# oresat-card.net
KiCad netlist of a schematic drawn in EAGLE
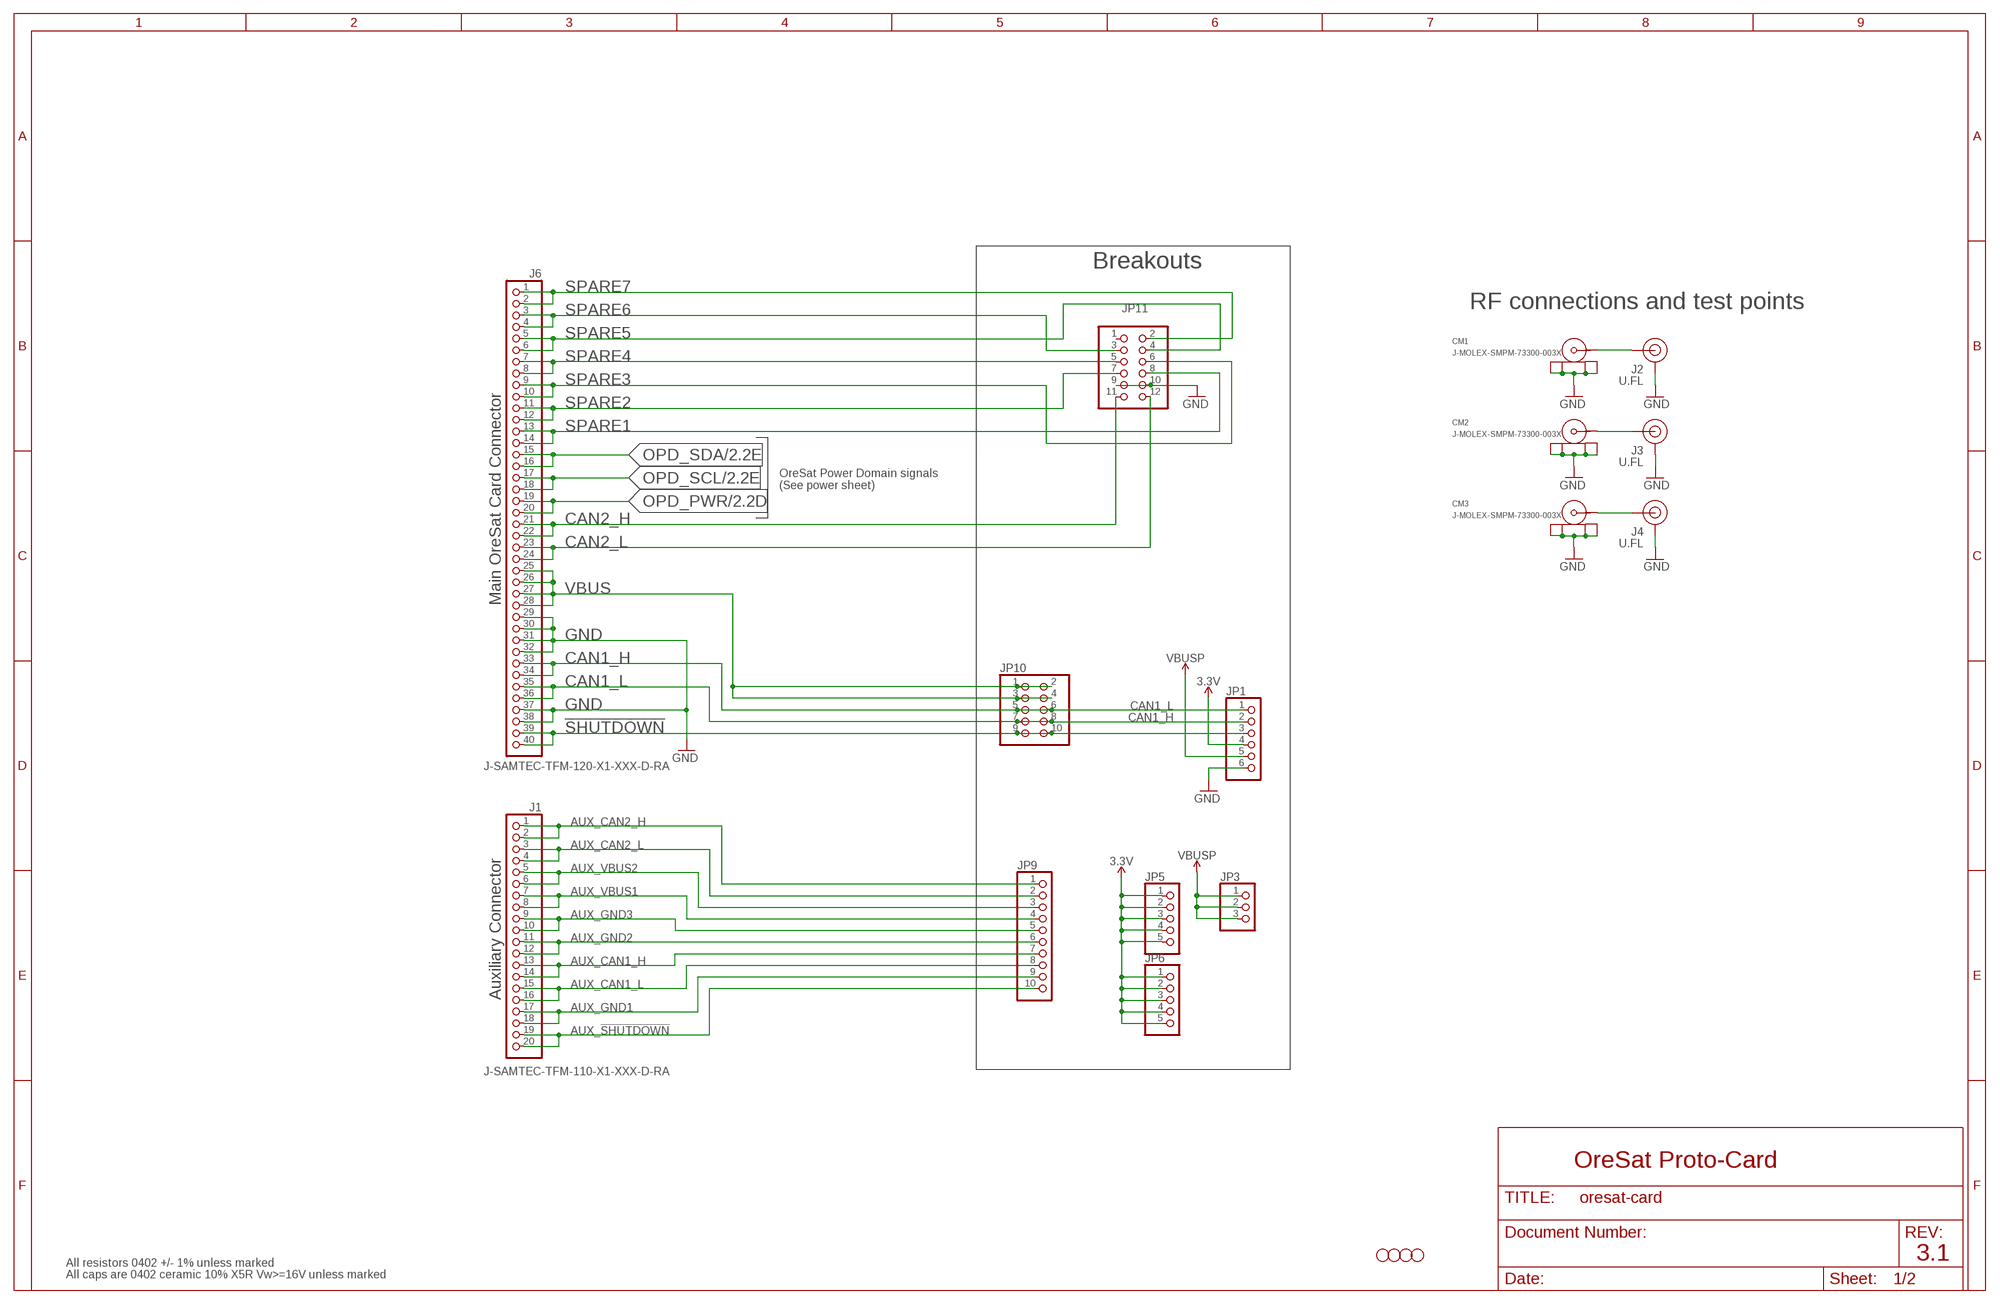
[diagram p0: schematic, sheet 1]
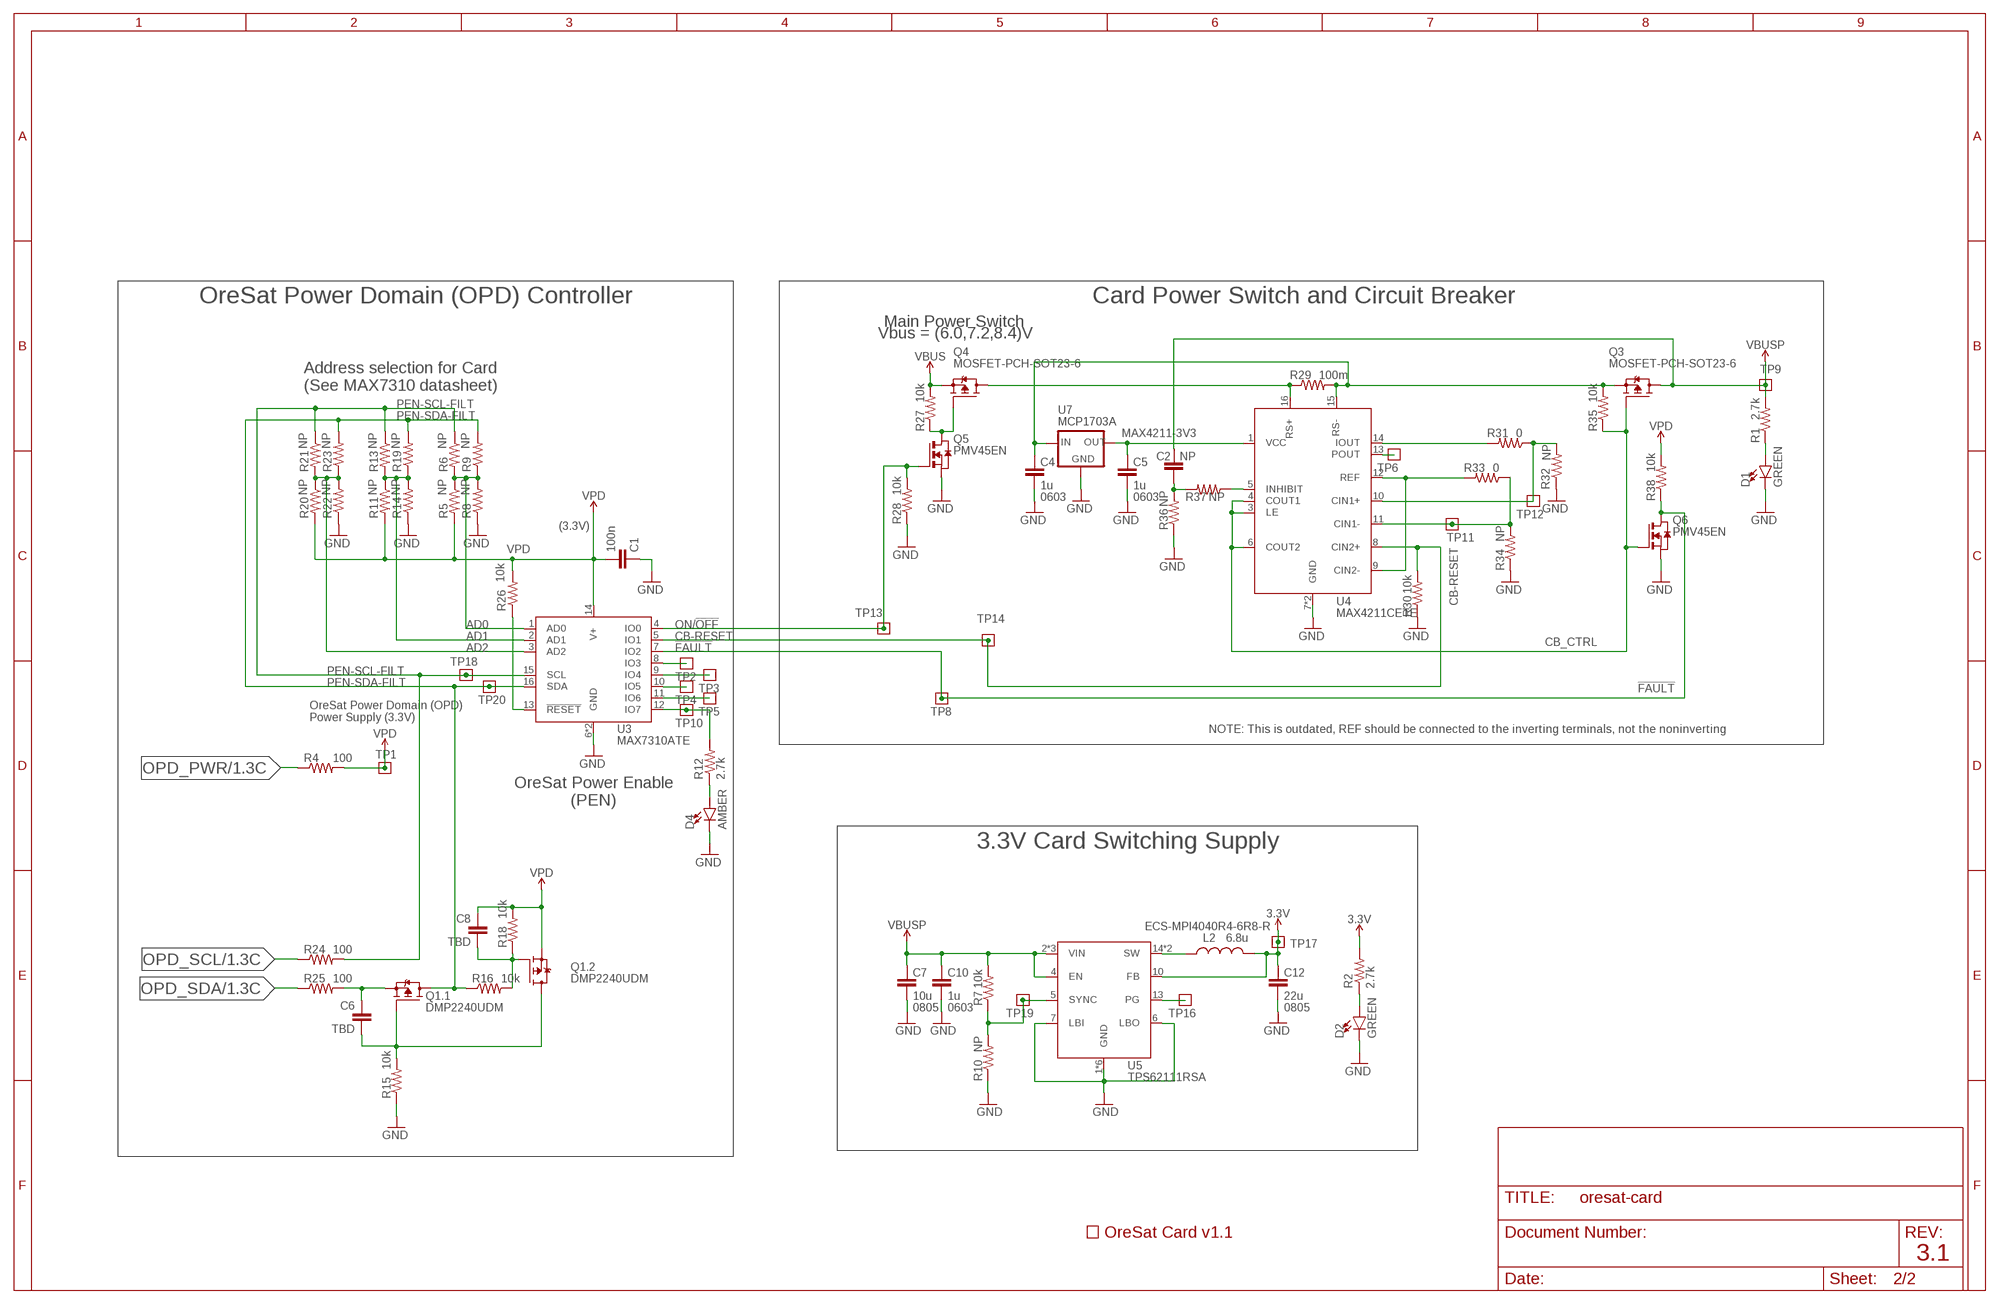
[diagram p1: schematic, sheet 2]

(export (version "E")
  (design (tool "Eeschema 10.0.6"))
  (components
    (comp (ref "CM1")
      (value "J-MOLEX-SMPM-73300-003X")
      (footprint "eagle-import:J-MOLEX-SMPM-073300-003X")
      (fields (field (name "MFR") "Molex") (field (name "MPN") "73300-0020"))
      (libsource (lib "eagle-import") (part "J-MOLEX-SMPM-73300-003X"))
    )
    (comp (ref "CM2")
      (value "J-MOLEX-SMPM-73300-003X")
      (footprint "eagle-import:J-MOLEX-SMPM-073300-003X")
      (fields (field (name "MFR") "Molex") (field (name "MPN") "73300-0020"))
      (libsource (lib "eagle-import") (part "J-MOLEX-SMPM-73300-003X"))
    )
    (comp (ref "CM3")
      (value "J-MOLEX-SMPM-73300-003X")
      (footprint "eagle-import:J-MOLEX-SMPM-073300-003X")
      (fields (field (name "MFR") "Molex") (field (name "MPN") "73300-0020"))
      (libsource (lib "eagle-import") (part "J-MOLEX-SMPM-73300-003X"))
    )
    (comp (ref "H1")
      (value "STAND-OFFTIGHT")
      (footprint "eagle-import:STAND-OFF-TIGHT")
      (libsource (lib "eagle-import") (part "STAND-OFFTIGHT"))
    )
    (comp (ref "H2")
      (value "STAND-OFFTIGHT")
      (footprint "eagle-import:STAND-OFF-TIGHT")
      (libsource (lib "eagle-import") (part "STAND-OFFTIGHT"))
    )
    (comp (ref "H3")
      (value "STAND-OFFTIGHT")
      (footprint "eagle-import:STAND-OFF-TIGHT")
      (libsource (lib "eagle-import") (part "STAND-OFFTIGHT"))
    )
    (comp (ref "H4")
      (value "STAND-OFFTIGHT")
      (footprint "eagle-import:STAND-OFF-TIGHT")
      (libsource (lib "eagle-import") (part "STAND-OFFTIGHT"))
    )
    (comp (ref "J1")
      (value "J-SAMTEC-TFM-110-X1-XXX-D-RA")
      (footprint "eagle-import:J-SAMTEC-TFM-110-X1-XXX-D-RA")
      (fields (field (name "MFR") "Samtec") (field (name "MPN") "TFM-110-01-L-D-RA "))
      (libsource (lib "eagle-import") (part "J-SAMTEC-TFM-110-X1-XXX-D-RA"))
    )
    (comp (ref "J2")
      (value "U.FL")
      (footprint "eagle-import:U.FL")
      (libsource (lib "eagle-import") (part "U.FL2PIN"))
    )
    (comp (ref "J3")
      (value "U.FL")
      (footprint "eagle-import:U.FL")
      (libsource (lib "eagle-import") (part "U.FL2PIN"))
    )
    (comp (ref "J4")
      (value "U.FL")
      (footprint "eagle-import:U.FL")
      (libsource (lib "eagle-import") (part "U.FL2PIN"))
    )
    (comp (ref "J6")
      (value "J-SAMTEC-TFM-120-X1-XXX-D-RA")
      (footprint "eagle-import:J-SAMTEC-TFM-120-X1-XXX-D-RA")
      (fields (field (name "MFR") "Samtec") (field (name "MPN") "TFM-120-01-L-D-RA"))
      (libsource (lib "eagle-import") (part "J-SAMTEC-TFM-120-X1-XXX-D-RA"))
    )
    (comp (ref "JP1")
      (value "PINHD-1X6")
      (footprint "eagle-import:1X06")
      (libsource (lib "eagle-import") (part "PINHD-1X6"))
    )
    (comp (ref "JP3")
      (value "PINHD-1X3")
      (footprint "eagle-import:1X03")
      (libsource (lib "eagle-import") (part "PINHD-1X3"))
    )
    (comp (ref "JP5")
      (value "PINHD-1X5")
      (footprint "eagle-import:1X05")
      (libsource (lib "eagle-import") (part "PINHD-1X5"))
    )
    (comp (ref "JP6")
      (value "PINHD-1X5")
      (footprint "eagle-import:1X05")
      (libsource (lib "eagle-import") (part "PINHD-1X5"))
    )
    (comp (ref "JP9")
      (value "PINHD-1X10")
      (footprint "eagle-import:1X10")
      (libsource (lib "eagle-import") (part "PINHD-1X10"))
    )
    (comp (ref "JP10")
      (value "PINHD-2X5")
      (footprint "eagle-import:2X05")
      (libsource (lib "eagle-import") (part "PINHD-2X5"))
    )
    (comp (ref "JP11")
      (value "PINHD-2X6")
      (footprint "eagle-import:2X06")
      (libsource (lib "eagle-import") (part "PINHD-2X6"))
    )
    (comp (ref "C1")
      (value "100n")
      (footprint "eagle-import:.0402-B-NOSILK")
      (fields (field (name "MFR") "Samsung") (field (name "MPN") "CL05B104KO5NNNC"))
      (libsource (lib "eagle-import") (part "rcl_custom_C-EU0402-B-NOSILK"))
    )
    (comp (ref "C2")
      (value "NP")
      (footprint "eagle-import:.0402-B-NOSILK")
      (fields (field (name "MFR") "Samsung") (field (name "MPN") "CL05B104KO5NNNC"))
      (libsource (lib "eagle-import") (part "rcl_custom_C-EU0402-B-NOSILK"))
    )
    (comp (ref "C4")
      (value "1u")
      (footprint "eagle-import:.0603-B-NOSILK")
      (fields (field (name "MFR") "Samsung") (field (name "MPN") "CL05B104KO5NNNC"))
      (libsource (lib "eagle-import") (part "C-EU0603-B-NOSILK"))
    )
    (comp (ref "C5")
      (value "1u")
      (footprint "eagle-import:.0603-B-NOSILK")
      (fields (field (name "MFR") "Samsung") (field (name "MPN") "CL05B104KO5NNNC"))
      (libsource (lib "eagle-import") (part "C-EU0603-B-NOSILK"))
    )
    (comp (ref "C6")
      (value "TBD")
      (footprint "eagle-import:.0402-B-NOSILK")
      (fields (field (name "MFR") "Samsung") (field (name "MPN") "CL05B104KO5NNNC"))
      (libsource (lib "eagle-import") (part "rcl_custom_C-EU0402-B-NOSILK"))
    )
    (comp (ref "C7")
      (value "10u")
      (footprint "eagle-import:.0805-B-NOSILK")
      (libsource (lib "eagle-import") (part "C-EU0805-B-NOSILK"))
    )
    (comp (ref "C8")
      (value "TBD")
      (footprint "eagle-import:.0402-B-NOSILK")
      (fields (field (name "MFR") "Samsung") (field (name "MPN") "CL05B104KO5NNNC"))
      (libsource (lib "eagle-import") (part "rcl_custom_C-EU0402-B-NOSILK"))
    )
    (comp (ref "C10")
      (value "1u")
      (footprint "eagle-import:.0603-B-NOSILK")
      (fields (field (name "MFR") "Samsung") (field (name "MPN") "CL05B104KO5NNNC"))
      (libsource (lib "eagle-import") (part "C-EU0603-B-NOSILK"))
    )
    (comp (ref "C12")
      (value "22u")
      (footprint "eagle-import:.0805-B-NOSILK")
      (libsource (lib "eagle-import") (part "C-EU0805-B-NOSILK"))
    )
    (comp (ref "D1")
      (value "GREEN")
      (footprint "eagle-import:LED-0603")
      (libsource (lib "eagle-import") (part "LED-GREEN0603"))
    )
    (comp (ref "D2")
      (value "GREEN")
      (footprint "eagle-import:LED-0603")
      (libsource (lib "eagle-import") (part "LED-GREEN0603"))
    )
    (comp (ref "D4")
      (value "AMBER")
      (footprint "eagle-import:LED-0603")
      (libsource (lib "eagle-import") (part "LED-GREEN0603"))
    )
    (comp (ref "L2")
      (value "6.8u")
      (footprint "eagle-import:ECS-MPI4040")
      (fields (field (name "MFR") "ECS") (field (name "MPN") "ECS-MPI4040R4-6R8-R"))
      (libsource (lib "eagle-import") (part "L-ECS-MPI4040"))
    )
    (comp (ref "Q1")
      (value "DMP2240UDM")
      (footprint "eagle-import:SOT23-6")
      (fields (field (name "MFR") "Diodes Inc") (field (name "MPN") "DMP2240UDM"))
      (libsource (lib "eagle-import") (part "Q-MOSFET-PCH-dual-SOT23-6_MOSFET-PCH-SOT23-6"))
    )
    (comp (ref "Q3")
      (value "MOSFET-PCH-SOT23-6")
      (footprint "eagle-import:SOT23-6")
      (fields (field (name "MFR") "Diodes Inc") (field (name "MPN") "DMP3050LVT-7"))
      (libsource (lib "eagle-import") (part "MOSFET-PCH-SOT23-6"))
    )
    (comp (ref "Q4")
      (value "MOSFET-PCH-SOT23-6")
      (footprint "eagle-import:SOT23-6")
      (fields (field (name "MFR") "Diodes Inc") (field (name "MPN") "DMP3050LVT-7"))
      (libsource (lib "eagle-import") (part "MOSFET-PCH-SOT23-6"))
    )
    (comp (ref "Q5")
      (value "PMV45EN")
      (footprint "eagle-import:SOT23")
      (libsource (lib "eagle-import") (part "PMV45EN"))
    )
    (comp (ref "Q6")
      (value "PMV45EN")
      (footprint "eagle-import:SOT23")
      (libsource (lib "eagle-import") (part "PMV45EN"))
    )
    (comp (ref "R1")
      (value "2.7k")
      (footprint "eagle-import:.0402-B-NOSILK")
      (fields (field (name "MFR") "Samsung") (field (name "MPN") "RC1005F6653CS"))
      (libsource (lib "eagle-import") (part "R-US_0402-B-NOSILK"))
    )
    (comp (ref "R2")
      (value "2.7k")
      (footprint "eagle-import:.0402-B-NOSILK")
      (fields (field (name "MFR") "Samsung") (field (name "MPN") "RC1005F6653CS"))
      (libsource (lib "eagle-import") (part "R-US_0402-B-NOSILK"))
    )
    (comp (ref "R4")
      (value "100")
      (footprint "eagle-import:.0402-B-NOSILK")
      (fields (field (name "MFR") "Samsung") (field (name "MPN") "RC1005F6653CS"))
      (libsource (lib "eagle-import") (part "R-US_0402-B-NOSILK"))
    )
    (comp (ref "R5")
      (value "NP")
      (footprint "eagle-import:.0402-B-NOSILK")
      (fields (field (name "MFR") "Samsung") (field (name "MPN") "RC1005F6653CS"))
      (libsource (lib "eagle-import") (part "R-US_0402-B-NOSILK"))
    )
    (comp (ref "R6")
      (value "NP")
      (footprint "eagle-import:.0402-B-NOSILK")
      (fields (field (name "MFR") "Samsung") (field (name "MPN") "RC1005F6653CS"))
      (libsource (lib "eagle-import") (part "R-US_0402-B-NOSILK"))
    )
    (comp (ref "R7")
      (value "10k")
      (footprint "eagle-import:.0402-B-NOSILK")
      (fields (field (name "MFR") "Samsung") (field (name "MPN") "RC1005F6653CS"))
      (libsource (lib "eagle-import") (part "R-US_0402-B-NOSILK"))
    )
    (comp (ref "R8")
      (value "NP")
      (footprint "eagle-import:.0402-B-NOSILK")
      (fields (field (name "MFR") "Samsung") (field (name "MPN") "RC1005F6653CS"))
      (libsource (lib "eagle-import") (part "R-US_0402-B-NOSILK"))
    )
    (comp (ref "R9")
      (value "NP")
      (footprint "eagle-import:.0402-B-NOSILK")
      (fields (field (name "MFR") "Samsung") (field (name "MPN") "RC1005F6653CS"))
      (libsource (lib "eagle-import") (part "R-US_0402-B-NOSILK"))
    )
    (comp (ref "R10")
      (value "NP")
      (footprint "eagle-import:.0402-B-NOSILK")
      (fields (field (name "MFR") "Samsung") (field (name "MPN") "RC1005F6653CS"))
      (libsource (lib "eagle-import") (part "R-US_0402-B-NOSILK"))
    )
    (comp (ref "R11")
      (value "NP")
      (footprint "eagle-import:.0402-B-NOSILK")
      (fields (field (name "MFR") "Samsung") (field (name "MPN") "RC1005F6653CS"))
      (libsource (lib "eagle-import") (part "R-US_0402-B-NOSILK"))
    )
    (comp (ref "R12")
      (value "2.7k")
      (footprint "eagle-import:.0402-B-NOSILK")
      (fields (field (name "MFR") "Samsung") (field (name "MPN") "RC1005F6653CS"))
      (libsource (lib "eagle-import") (part "R-US_0402-B-NOSILK"))
    )
    (comp (ref "R13")
      (value "NP")
      (footprint "eagle-import:.0402-B-NOSILK")
      (fields (field (name "MFR") "Samsung") (field (name "MPN") "RC1005F6653CS"))
      (libsource (lib "eagle-import") (part "R-US_0402-B-NOSILK"))
    )
    (comp (ref "R14")
      (value "NP")
      (footprint "eagle-import:.0402-B-NOSILK")
      (fields (field (name "MFR") "Samsung") (field (name "MPN") "RC1005F6653CS"))
      (libsource (lib "eagle-import") (part "R-US_0402-B-NOSILK"))
    )
    (comp (ref "R15")
      (value "10k")
      (footprint "eagle-import:.0402-B-NOSILK")
      (fields (field (name "MFR") "Samsung") (field (name "MPN") "RC1005F6653CS"))
      (libsource (lib "eagle-import") (part "R-US_0402-B-NOSILK"))
    )
    (comp (ref "R16")
      (value "10k")
      (footprint "eagle-import:.0402-B-NOSILK")
      (fields (field (name "MFR") "Samsung") (field (name "MPN") "RC1005F6653CS"))
      (libsource (lib "eagle-import") (part "R-US_0402-B-NOSILK"))
    )
    (comp (ref "R18")
      (value "10k")
      (footprint "eagle-import:.0402-B-NOSILK")
      (fields (field (name "MFR") "Samsung") (field (name "MPN") "RC1005F6653CS"))
      (libsource (lib "eagle-import") (part "R-US_0402-B-NOSILK"))
    )
    (comp (ref "R19")
      (value "NP")
      (footprint "eagle-import:.0402-B-NOSILK")
      (fields (field (name "MFR") "Samsung") (field (name "MPN") "RC1005F6653CS"))
      (libsource (lib "eagle-import") (part "R-US_0402-B-NOSILK"))
    )
    (comp (ref "R20")
      (value "NP")
      (footprint "eagle-import:.0402-B-NOSILK")
      (fields (field (name "MFR") "Samsung") (field (name "MPN") "RC1005F6653CS"))
      (libsource (lib "eagle-import") (part "R-US_0402-B-NOSILK"))
    )
    (comp (ref "R21")
      (value "NP")
      (footprint "eagle-import:.0402-B-NOSILK")
      (fields (field (name "MFR") "Samsung") (field (name "MPN") "RC1005F6653CS"))
      (libsource (lib "eagle-import") (part "R-US_0402-B-NOSILK"))
    )
    (comp (ref "R22")
      (value "NP")
      (footprint "eagle-import:.0402-B-NOSILK")
      (fields (field (name "MFR") "Samsung") (field (name "MPN") "RC1005F6653CS"))
      (libsource (lib "eagle-import") (part "R-US_0402-B-NOSILK"))
    )
    (comp (ref "R23")
      (value "NP")
      (footprint "eagle-import:.0402-B-NOSILK")
      (fields (field (name "MFR") "Samsung") (field (name "MPN") "RC1005F6653CS"))
      (libsource (lib "eagle-import") (part "R-US_0402-B-NOSILK"))
    )
    (comp (ref "R24")
      (value "100")
      (footprint "eagle-import:.0402-B-NOSILK")
      (fields (field (name "MFR") "Samsung") (field (name "MPN") "RC1005F6653CS"))
      (libsource (lib "eagle-import") (part "R-US_0402-B-NOSILK"))
    )
    (comp (ref "R25")
      (value "100")
      (footprint "eagle-import:.0402-B-NOSILK")
      (fields (field (name "MFR") "Samsung") (field (name "MPN") "RC1005F6653CS"))
      (libsource (lib "eagle-import") (part "R-US_0402-B-NOSILK"))
    )
    (comp (ref "R26")
      (value "10k")
      (footprint "eagle-import:.0402-B-NOSILK")
      (fields (field (name "MFR") "Samsung") (field (name "MPN") "RC1005F6653CS"))
      (libsource (lib "eagle-import") (part "R-US_0402-B-NOSILK"))
    )
    (comp (ref "R27")
      (value "10k")
      (footprint "eagle-import:.0402-B-NOSILK")
      (fields (field (name "MFR") "Samsung") (field (name "MPN") "RC1005F6653CS"))
      (libsource (lib "eagle-import") (part "R-US_0402-B-NOSILK"))
    )
    (comp (ref "R28")
      (value "10k")
      (footprint "eagle-import:.0402-B-NOSILK")
      (fields (field (name "MFR") "Samsung") (field (name "MPN") "RC1005F6653CS"))
      (libsource (lib "eagle-import") (part "R-US_0402-B-NOSILK"))
    )
    (comp (ref "R29")
      (value "100m")
      (footprint "eagle-import:R1206")
      (libsource (lib "eagle-import") (part "R-US_R1206"))
    )
    (comp (ref "R30")
      (value "10k")
      (footprint "eagle-import:.0402-B-NOSILK")
      (fields (field (name "MFR") "Samsung") (field (name "MPN") "RC1005F6653CS"))
      (libsource (lib "eagle-import") (part "R-US_0402-B-NOSILK"))
    )
    (comp (ref "R31")
      (value "0")
      (footprint "eagle-import:.0402-B-NOSILK")
      (fields (field (name "MFR") "Samsung") (field (name "MPN") "RC1005F6653CS"))
      (libsource (lib "eagle-import") (part "R-US_0402-B-NOSILK"))
    )
    (comp (ref "R32")
      (value "NP")
      (footprint "eagle-import:.0402-B-NOSILK")
      (fields (field (name "MFR") "Samsung") (field (name "MPN") "RC1005F6653CS"))
      (libsource (lib "eagle-import") (part "R-US_0402-B-NOSILK"))
    )
    (comp (ref "R33")
      (value "0")
      (footprint "eagle-import:.0402-B-NOSILK")
      (fields (field (name "MFR") "Samsung") (field (name "MPN") "RC1005F6653CS"))
      (libsource (lib "eagle-import") (part "R-US_0402-B-NOSILK"))
    )
    (comp (ref "R34")
      (value "NP")
      (footprint "eagle-import:.0402-B-NOSILK")
      (fields (field (name "MFR") "Samsung") (field (name "MPN") "RC1005F6653CS"))
      (libsource (lib "eagle-import") (part "R-US_0402-B-NOSILK"))
    )
    (comp (ref "R35")
      (value "10k")
      (footprint "eagle-import:.0402-B-NOSILK")
      (fields (field (name "MFR") "Samsung") (field (name "MPN") "RC1005F6653CS"))
      (libsource (lib "eagle-import") (part "R-US_0402-B-NOSILK"))
    )
    (comp (ref "R36")
      (value "NP")
      (footprint "eagle-import:.0402-B-NOSILK")
      (fields (field (name "MFR") "Samsung") (field (name "MPN") "RC1005F6653CS"))
      (libsource (lib "eagle-import") (part "R-US_0402-B-NOSILK"))
    )
    (comp (ref "R37")
      (value "NP")
      (footprint "eagle-import:.0402-B-NOSILK")
      (fields (field (name "MFR") "Samsung") (field (name "MPN") "RC1005F6653CS"))
      (libsource (lib "eagle-import") (part "R-US_0402-B-NOSILK"))
    )
    (comp (ref "R38")
      (value "10k")
      (footprint "eagle-import:.0402-B-NOSILK")
      (fields (field (name "MFR") "Samsung") (field (name "MPN") "RC1005F6653CS"))
      (libsource (lib "eagle-import") (part "R-US_0402-B-NOSILK"))
    )
    (comp (ref "TP1")
      (value "TEST-POINT")
      (footprint "eagle-import:2MM-TEST-POINT")
      (libsource (lib "eagle-import") (part "TEST-POINT"))
    )
    (comp (ref "TP2")
      (value "TEST-POINT")
      (footprint "eagle-import:2MM-TEST-POINT")
      (libsource (lib "eagle-import") (part "TEST-POINT"))
    )
    (comp (ref "TP3")
      (value "TEST-POINT")
      (footprint "eagle-import:2MM-TEST-POINT")
      (libsource (lib "eagle-import") (part "TEST-POINT"))
    )
    (comp (ref "TP4")
      (value "TEST-POINT")
      (footprint "eagle-import:2MM-TEST-POINT")
      (libsource (lib "eagle-import") (part "TEST-POINT"))
    )
    (comp (ref "TP5")
      (value "TEST-POINT")
      (footprint "eagle-import:2MM-TEST-POINT")
      (libsource (lib "eagle-import") (part "TEST-POINT"))
    )
    (comp (ref "TP6")
      (value "TEST-POINT")
      (footprint "eagle-import:2MM-TEST-POINT")
      (libsource (lib "eagle-import") (part "TEST-POINT"))
    )
    (comp (ref "TP8")
      (value "TEST-POINT")
      (footprint "eagle-import:2MM-TEST-POINT")
      (libsource (lib "eagle-import") (part "TEST-POINT"))
    )
    (comp (ref "TP9")
      (value "TEST-POINT")
      (footprint "eagle-import:2MM-TEST-POINT")
      (libsource (lib "eagle-import") (part "TEST-POINT"))
    )
    (comp (ref "TP10")
      (value "TEST-POINT")
      (footprint "eagle-import:2MM-TEST-POINT")
      (libsource (lib "eagle-import") (part "TEST-POINT"))
    )
    (comp (ref "TP11")
      (value "TEST-POINT")
      (footprint "eagle-import:2MM-TEST-POINT")
      (libsource (lib "eagle-import") (part "TEST-POINT"))
    )
    (comp (ref "TP12")
      (value "TEST-POINT")
      (footprint "eagle-import:2MM-TEST-POINT")
      (libsource (lib "eagle-import") (part "TEST-POINT"))
    )
    (comp (ref "TP13")
      (value "TEST-POINT")
      (footprint "eagle-import:2MM-TEST-POINT")
      (libsource (lib "eagle-import") (part "TEST-POINT"))
    )
    (comp (ref "TP14")
      (value "TEST-POINT")
      (footprint "eagle-import:2MM-TEST-POINT")
      (libsource (lib "eagle-import") (part "TEST-POINT"))
    )
    (comp (ref "TP16")
      (value "TEST-POINT")
      (footprint "eagle-import:2MM-TEST-POINT")
      (libsource (lib "eagle-import") (part "TEST-POINT"))
    )
    (comp (ref "TP17")
      (value "TEST-POINT")
      (footprint "eagle-import:2MM-TEST-POINT")
      (libsource (lib "eagle-import") (part "TEST-POINT"))
    )
    (comp (ref "TP18")
      (value "TEST-POINT")
      (footprint "eagle-import:2MM-TEST-POINT")
      (libsource (lib "eagle-import") (part "TEST-POINT"))
    )
    (comp (ref "TP19")
      (value "TEST-POINT")
      (footprint "eagle-import:2MM-TEST-POINT")
      (libsource (lib "eagle-import") (part "TEST-POINT"))
    )
    (comp (ref "TP20")
      (value "TEST-POINT")
      (footprint "eagle-import:2MM-TEST-POINT")
      (libsource (lib "eagle-import") (part "TEST-POINT"))
    )
    (comp (ref "U$1")
      (value "ORESAT-CARD-V1.1-3XRF")
      (footprint "eagle-import:ORESAT-CARD-V1.1-3XRF")
      (libsource (lib "eagle-import") (part "ORESAT-CARD-V1.1-3XRF"))
    )
    (comp (ref "U3")
      (value "MAX7310ATE")
      (footprint "eagle-import:QFN65P400X400X80-17T210")
      (fields (field (name "MFR") "Maxim"))
      (libsource (lib "eagle-import") (part "MAX7310"))
    )
    (comp (ref "U4")
      (value "MAX4211CETE")
      (footprint "eagle-import:QFN65P400X400X80-17T210")
      (fields (field (name "MFR") "Maxim"))
      (libsource (lib "eagle-import") (part "MAX4211"))
    )
    (comp (ref "U5")
      (value "TPS62111RSA")
      (footprint "eagle-import:S-PVQFN-16")
      (fields (field (name "MFR") "TI"))
      (libsource (lib "eagle-import") (part "TPS6211X"))
    )
    (comp (ref "U7")
      (value "MCP1703A")
      (footprint "eagle-import:SOT23")
      (fields (field (name "MFR") "Microchip") (field (name "MPN") "MCP1703AT-3302E/CB"))
      (libsource (lib "eagle-import") (part "XC63FPM"))
    )
  )
  (nets
    (net (code "1") (name "3.3V") (class "Default")
      (node (ref "C12") (pin "1") (pinfunction "1_1") (pintype "passive"))
      (node (ref "JP1") (pin "4") (pinfunction "4_4") (pintype "passive"))
      (node (ref "JP5") (pin "1") (pinfunction "1_1") (pintype "passive"))
      (node (ref "JP5") (pin "2") (pinfunction "2_2") (pintype "passive"))
      (node (ref "JP5") (pin "3") (pinfunction "3_3") (pintype "passive"))
      (node (ref "JP5") (pin "4") (pinfunction "4_4") (pintype "passive"))
      (node (ref "JP5") (pin "5") (pinfunction "5_5") (pintype "passive"))
      (node (ref "JP6") (pin "1") (pinfunction "1_1") (pintype "passive"))
      (node (ref "JP6") (pin "2") (pinfunction "2_2") (pintype "passive"))
      (node (ref "JP6") (pin "3") (pinfunction "3_3") (pintype "passive"))
      (node (ref "JP6") (pin "4") (pinfunction "4_4") (pintype "passive"))
      (node (ref "JP6") (pin "5") (pinfunction "5_5") (pintype "passive"))
      (node (ref "L2") (pin "2") (pinfunction "2_2") (pintype "passive"))
      (node (ref "R2") (pin "2") (pinfunction "2_2") (pintype "passive"))
      (node (ref "TP17") (pin "1") (pinfunction "1_1") (pintype "passive"))
      (node (ref "U5") (pin "10") (pinfunction "FB_10") (pintype "input"))
    )
    (net (code "2") (name "AD0") (class "Default")
      (node (ref "R5") (pin "1") (pinfunction "1_1") (pintype "passive"))
      (node (ref "R6") (pin "2") (pinfunction "2_2") (pintype "passive"))
      (node (ref "R8") (pin "2") (pinfunction "2_2") (pintype "passive"))
      (node (ref "R9") (pin "1") (pinfunction "1_1") (pintype "passive"))
      (node (ref "U3") (pin "1") (pinfunction "AD0_1") (pintype "input"))
    )
    (net (code "3") (name "AD1") (class "Default")
      (node (ref "R11") (pin "1") (pinfunction "1_1") (pintype "passive"))
      (node (ref "R13") (pin "2") (pinfunction "2_2") (pintype "passive"))
      (node (ref "R14") (pin "2") (pinfunction "2_2") (pintype "passive"))
      (node (ref "R19") (pin "1") (pinfunction "1_1") (pintype "passive"))
      (node (ref "U3") (pin "2") (pinfunction "AD1_2") (pintype "input"))
    )
    (net (code "4") (name "AD2") (class "Default")
      (node (ref "R20") (pin "1") (pinfunction "1_1") (pintype "passive"))
      (node (ref "R21") (pin "2") (pinfunction "2_2") (pintype "passive"))
      (node (ref "R22") (pin "2") (pinfunction "2_2") (pintype "passive"))
      (node (ref "R23") (pin "1") (pinfunction "1_1") (pintype "passive"))
      (node (ref "U3") (pin "3") (pinfunction "AD2_3") (pintype "input"))
    )
    (net (code "5") (name "AUX_CAN1_H") (class "Default")
      (node (ref "J1") (pin "13") (pinfunction "13_13") (pintype "passive"))
      (node (ref "J1") (pin "14") (pinfunction "14_14") (pintype "passive"))
      (node (ref "JP9") (pin "7") (pinfunction "7_7") (pintype "passive"))
    )
    (net (code "6") (name "AUX_CAN1_L") (class "Default")
      (node (ref "J1") (pin "15") (pinfunction "15_15") (pintype "passive"))
      (node (ref "J1") (pin "16") (pinfunction "16_16") (pintype "passive"))
      (node (ref "JP9") (pin "8") (pinfunction "8_8") (pintype "passive"))
    )
    (net (code "7") (name "AUX_CAN2_H") (class "Default")
      (node (ref "J1") (pin "1") (pinfunction "1_1") (pintype "passive"))
      (node (ref "J1") (pin "2") (pinfunction "2_2") (pintype "passive"))
      (node (ref "JP9") (pin "1") (pinfunction "1_1") (pintype "passive"))
    )
    (net (code "8") (name "AUX_CAN2_L") (class "Default")
      (node (ref "J1") (pin "3") (pinfunction "3_3") (pintype "passive"))
      (node (ref "J1") (pin "4") (pinfunction "4_4") (pintype "passive"))
      (node (ref "JP9") (pin "2") (pinfunction "2_2") (pintype "passive"))
    )
    (net (code "9") (name "AUX_GND1") (class "Default")
      (node (ref "J1") (pin "17") (pinfunction "17_17") (pintype "passive"))
      (node (ref "J1") (pin "18") (pinfunction "18_18") (pintype "passive"))
      (node (ref "JP9") (pin "9") (pinfunction "9_9") (pintype "passive"))
    )
    (net (code "10") (name "AUX_GND2") (class "Default")
      (node (ref "J1") (pin "11") (pinfunction "11_11") (pintype "passive"))
      (node (ref "J1") (pin "12") (pinfunction "12_12") (pintype "passive"))
      (node (ref "JP9") (pin "6") (pinfunction "6_6") (pintype "passive"))
    )
    (net (code "11") (name "AUX_GND3") (class "Default")
      (node (ref "J1") (pin "10") (pinfunction "10_10") (pintype "passive"))
      (node (ref "J1") (pin "9") (pinfunction "9_9") (pintype "passive"))
      (node (ref "JP9") (pin "5") (pinfunction "5_5") (pintype "passive"))
    )
    (net (code "12") (name "AUX_VBUS1") (class "Default")
      (node (ref "J1") (pin "7") (pinfunction "7_7") (pintype "passive"))
      (node (ref "J1") (pin "8") (pinfunction "8_8") (pintype "passive"))
      (node (ref "JP9") (pin "4") (pinfunction "4_4") (pintype "passive"))
    )
    (net (code "13") (name "AUX_VBUS2") (class "Default")
      (node (ref "J1") (pin "5") (pinfunction "5_5") (pintype "passive"))
      (node (ref "J1") (pin "6") (pinfunction "6_6") (pintype "passive"))
      (node (ref "JP9") (pin "3") (pinfunction "3_3") (pintype "passive"))
    )
    (net (code "14") (name "AUX_~{SHUTDOWN}") (class "Default")
      (node (ref "J1") (pin "19") (pinfunction "19_19") (pintype "passive"))
      (node (ref "J1") (pin "20") (pinfunction "20_20") (pintype "passive"))
      (node (ref "JP9") (pin "10") (pinfunction "10_10") (pintype "passive"))
    )
    (net (code "15") (name "CAN1_H") (class "Default")
      (node (ref "J6") (pin "33") (pinfunction "33_33") (pintype "passive"))
      (node (ref "J6") (pin "34") (pinfunction "34_34") (pintype "passive"))
      (node (ref "JP1") (pin "1") (pinfunction "1_1") (pintype "passive"))
      (node (ref "JP10") (pin "5") (pinfunction "5_5") (pintype "passive"))
      (node (ref "JP10") (pin "6") (pinfunction "6_6") (pintype "passive"))
    )
    (net (code "16") (name "CAN1_L") (class "Default")
      (node (ref "J6") (pin "35") (pinfunction "35_35") (pintype "passive"))
      (node (ref "J6") (pin "36") (pinfunction "36_36") (pintype "passive"))
      (node (ref "JP1") (pin "2") (pinfunction "2_2") (pintype "passive"))
      (node (ref "JP10") (pin "7") (pinfunction "7_7") (pintype "passive"))
      (node (ref "JP10") (pin "8") (pinfunction "8_8") (pintype "passive"))
    )
    (net (code "17") (name "CAN2_H") (class "Default")
      (node (ref "J6") (pin "21") (pinfunction "21_21") (pintype "passive"))
      (node (ref "J6") (pin "22") (pinfunction "22_22") (pintype "passive"))
      (node (ref "JP11") (pin "11") (pinfunction "11_11") (pintype "passive"))
    )
    (net (code "18") (name "CAN2_L") (class "Default")
      (node (ref "J6") (pin "23") (pinfunction "23_23") (pintype "passive"))
      (node (ref "J6") (pin "24") (pinfunction "24_24") (pintype "passive"))
      (node (ref "JP11") (pin "12") (pinfunction "12_12") (pintype "passive"))
    )
    (net (code "19") (name "CB-RESET") (class "Default")
      (node (ref "R30") (pin "2") (pinfunction "2_2") (pintype "passive"))
      (node (ref "TP14") (pin "1") (pinfunction "1_1") (pintype "passive"))
      (node (ref "U3") (pin "5") (pinfunction "IO1_5") (pintype "bidirectional"))
      (node (ref "U4") (pin "8") (pinfunction "CIN2+_8") (pintype "input"))
    )
    (net (code "20") (name "CB_CTRL") (class "Default")
      (node (ref "Q3") (pin "3") (pinfunction "G_3") (pintype "passive"))
      (node (ref "Q6") (pin "1") (pinfunction "G_1") (pintype "passive"))
      (node (ref "R35") (pin "1") (pinfunction "1_1") (pintype "passive"))
      (node (ref "U4") (pin "3") (pinfunction "LE_3") (pintype "input"))
      (node (ref "U4") (pin "4") (pinfunction "COUT1_4") (pintype "open_collector"))
      (node (ref "U4") (pin "6") (pinfunction "COUT2_6") (pintype "open_collector"))
    )
    (net (code "21") (name "GND") (class "Default")
      (node (ref "C1") (pin "1") (pinfunction "1_1") (pintype "passive"))
      (node (ref "C10") (pin "2") (pinfunction "2_2") (pintype "passive"))
      (node (ref "C12") (pin "2") (pinfunction "2_2") (pintype "passive"))
      (node (ref "C4") (pin "2") (pinfunction "2_2") (pintype "passive"))
      (node (ref "C5") (pin "2") (pinfunction "2_2") (pintype "passive"))
      (node (ref "C7") (pin "2") (pinfunction "2_2") (pintype "passive"))
      (node (ref "CM1") (pin "P$1") (pinfunction "SHIELD3_P$1") (pintype "passive"))
      (node (ref "CM1") (pin "P$2") (pinfunction "SHIELD2_P$2") (pintype "passive"))
      (node (ref "CM1") (pin "P$3") (pinfunction "SHIELD1_P$3") (pintype "passive"))
      (node (ref "CM1") (pin "P$4") (pinfunction "SHIELD_P$4") (pintype "passive"))
      (node (ref "CM2") (pin "P$1") (pinfunction "SHIELD3_P$1") (pintype "passive"))
      (node (ref "CM2") (pin "P$2") (pinfunction "SHIELD2_P$2") (pintype "passive"))
      (node (ref "CM2") (pin "P$3") (pinfunction "SHIELD1_P$3") (pintype "passive"))
      (node (ref "CM2") (pin "P$4") (pinfunction "SHIELD_P$4") (pintype "passive"))
      (node (ref "CM3") (pin "P$1") (pinfunction "SHIELD3_P$1") (pintype "passive"))
      (node (ref "CM3") (pin "P$2") (pinfunction "SHIELD2_P$2") (pintype "passive"))
      (node (ref "CM3") (pin "P$3") (pinfunction "SHIELD1_P$3") (pintype "passive"))
      (node (ref "CM3") (pin "P$4") (pinfunction "SHIELD_P$4") (pintype "passive"))
      (node (ref "D1") (pin "C") (pinfunction "C_C") (pintype "passive"))
      (node (ref "D2") (pin "C") (pinfunction "C_C") (pintype "passive"))
      (node (ref "D4") (pin "C") (pinfunction "C_C") (pintype "passive"))
      (node (ref "J2") (pin "1") (pinfunction "GND_1") (pintype "bidirectional"))
      (node (ref "J2") (pin "2") (pinfunction "GND_2") (pintype "bidirectional"))
      (node (ref "J3") (pin "1") (pinfunction "GND_1") (pintype "bidirectional"))
      (node (ref "J3") (pin "2") (pinfunction "GND_2") (pintype "bidirectional"))
      (node (ref "J4") (pin "1") (pinfunction "GND_1") (pintype "bidirectional"))
      (node (ref "J4") (pin "2") (pinfunction "GND_2") (pintype "bidirectional"))
      (node (ref "J6") (pin "29") (pinfunction "29_29") (pintype "passive"))
      (node (ref "J6") (pin "30") (pinfunction "30_30") (pintype "passive"))
      (node (ref "J6") (pin "31") (pinfunction "31_31") (pintype "passive"))
      (node (ref "J6") (pin "32") (pinfunction "32_32") (pintype "passive"))
      (node (ref "J6") (pin "37") (pinfunction "37_37") (pintype "passive"))
      (node (ref "J6") (pin "38") (pinfunction "38_38") (pintype "passive"))
      (node (ref "JP1") (pin "6") (pinfunction "6_6") (pintype "passive"))
      (node (ref "JP11") (pin "10") (pinfunction "10_10") (pintype "passive"))
      (node (ref "JP11") (pin "9") (pinfunction "9_9") (pintype "passive"))
      (node (ref "Q5") (pin "2") (pinfunction "S_2") (pintype "passive"))
      (node (ref "Q6") (pin "2") (pinfunction "S_2") (pintype "passive"))
      (node (ref "R10") (pin "1") (pinfunction "1_1") (pintype "passive"))
      (node (ref "R14") (pin "1") (pinfunction "1_1") (pintype "passive"))
      (node (ref "R15") (pin "1") (pinfunction "1_1") (pintype "passive"))
      (node (ref "R22") (pin "1") (pinfunction "1_1") (pintype "passive"))
      (node (ref "R28") (pin "1") (pinfunction "1_1") (pintype "passive"))
      (node (ref "R30") (pin "1") (pinfunction "1_1") (pintype "passive"))
      (node (ref "R32") (pin "1") (pinfunction "1_1") (pintype "passive"))
      (node (ref "R34") (pin "1") (pinfunction "1_1") (pintype "passive"))
      (node (ref "R36") (pin "1") (pinfunction "1_1") (pintype "passive"))
      (node (ref "R8") (pin "1") (pinfunction "1_1") (pintype "passive"))
      (node (ref "U3") (pin "6") (pinfunction "GND_6") (pintype "power_in"))
      (node (ref "U3") (pin "EPAD") (pinfunction "GND_EPAD") (pintype "power_in"))
      (node (ref "U4") (pin "7") (pinfunction "GND_7") (pintype "power_in"))
      (node (ref "U4") (pin "EPAD") (pinfunction "GND_EPAD") (pintype "power_in"))
      (node (ref "U5") (pin "1") (pinfunction "GND_1") (pintype "power_in"))
      (node (ref "U5") (pin "11") (pinfunction "GND_11") (pintype "power_in"))
      (node (ref "U5") (pin "12") (pinfunction "GND_12") (pintype "power_in"))
      (node (ref "U5") (pin "16") (pinfunction "GND_16") (pintype "power_in"))
      (node (ref "U5") (pin "6") (pinfunction "LBO_6") (pintype "open_collector"))
      (node (ref "U5") (pin "7") (pinfunction "LBI_7") (pintype "input"))
      (node (ref "U5") (pin "9") (pinfunction "GND_9") (pintype "power_in"))
      (node (ref "U5") (pin "PAD") (pinfunction "GND_PAD") (pintype "power_in"))
      (node (ref "U7") (pin "1") (pinfunction "GND_1") (pintype "input"))
    )
    (net (code "22") (name "MAX4211-3V3") (class "Default")
      (node (ref "C5") (pin "1") (pinfunction "1_1") (pintype "passive"))
      (node (ref "U4") (pin "1") (pinfunction "VCC_1") (pintype "power_in"))
      (node (ref "U7") (pin "2") (pinfunction "OUT_2") (pintype "passive"))
    )
    (net (code "23") (name "Net-(C2-Pad1)") (class "Default")
      (node (ref "C2") (pin "1") (pinfunction "1_1") (pintype "passive"))
      (node (ref "R36") (pin "2") (pinfunction "2_2") (pintype "passive"))
      (node (ref "R37") (pin "2") (pinfunction "2_2") (pintype "passive"))
    )
    (net (code "24") (name "Net-(CM1-CENTER)") (class "Default")
      (node (ref "CM1") (pin "RF") (pinfunction "CENTER_RF") (pintype "passive"))
      (node (ref "J2") (pin "FEED") (pinfunction "SIGNAL_FEED") (pintype "bidirectional"))
    )
    (net (code "25") (name "Net-(CM2-CENTER)") (class "Default")
      (node (ref "CM2") (pin "RF") (pinfunction "CENTER_RF") (pintype "passive"))
      (node (ref "J3") (pin "FEED") (pinfunction "SIGNAL_FEED") (pintype "bidirectional"))
    )
    (net (code "26") (name "Net-(CM3-CENTER)") (class "Default")
      (node (ref "CM3") (pin "RF") (pinfunction "CENTER_RF") (pintype "passive"))
      (node (ref "J4") (pin "FEED") (pinfunction "SIGNAL_FEED") (pintype "bidirectional"))
    )
    (net (code "27") (name "Net-(D1-PadA)") (class "Default")
      (node (ref "D1") (pin "A") (pinfunction "A_A") (pintype "passive"))
      (node (ref "R1") (pin "1") (pinfunction "1_1") (pintype "passive"))
    )
    (net (code "28") (name "Net-(D2-PadA)") (class "Default")
      (node (ref "D2") (pin "A") (pinfunction "A_A") (pintype "passive"))
      (node (ref "R2") (pin "1") (pinfunction "1_1") (pintype "passive"))
    )
    (net (code "29") (name "Net-(D4-PadA)") (class "Default")
      (node (ref "D4") (pin "A") (pinfunction "A_A") (pintype "passive"))
      (node (ref "R12") (pin "1") (pinfunction "1_1") (pintype "passive"))
    )
    (net (code "30") (name "Net-(L2-Pad1)") (class "Default")
      (node (ref "L2") (pin "1") (pinfunction "1_1") (pintype "passive"))
      (node (ref "U5") (pin "14") (pinfunction "SW_14") (pintype "output"))
      (node (ref "U5") (pin "15") (pinfunction "SW_15") (pintype "output"))
    )
    (net (code "31") (name "Net-(Q1A-G)") (class "Default")
      (node (ref "C6") (pin "2") (pinfunction "2_2") (pintype "passive"))
      (node (ref "Q1") (pin "1") (pinfunction "G_1") (pintype "passive"))
      (node (ref "Q1") (pin "4") (pinfunction "D_4") (pintype "passive"))
      (node (ref "R15") (pin "2") (pinfunction "2_2") (pintype "passive"))
    )
    (net (code "32") (name "Net-(Q1A-S)") (class "Default")
      (node (ref "C6") (pin "1") (pinfunction "1_1") (pintype "passive"))
      (node (ref "Q1") (pin "5") (pinfunction "S_5") (pintype "passive"))
      (node (ref "R25") (pin "2") (pinfunction "2_2") (pintype "passive"))
    )
    (net (code "33") (name "Net-(Q1B-G)") (class "Default")
      (node (ref "C8") (pin "2") (pinfunction "2_2") (pintype "passive"))
      (node (ref "Q1") (pin "3") (pinfunction "G_3") (pintype "passive"))
      (node (ref "R16") (pin "2") (pinfunction "2_2") (pintype "passive"))
      (node (ref "R18") (pin "1") (pinfunction "1_1") (pintype "passive"))
    )
    (net (code "34") (name "Net-(Q3-S)") (class "Default")
      (node (ref "C4") (pin "1") (pinfunction "1_1") (pintype "passive"))
      (node (ref "Q3") (pin "4") (pinfunction "S_4") (pintype "passive"))
      (node (ref "R29") (pin "2") (pinfunction "2_2") (pintype "passive"))
      (node (ref "R35") (pin "2") (pinfunction "2_2") (pintype "passive"))
      (node (ref "U4") (pin "15") (pinfunction "RS-_15") (pintype "passive"))
      (node (ref "U7") (pin "3") (pinfunction "IN_3") (pintype "input"))
    )
    (net (code "35") (name "Net-(Q4-G)") (class "Default")
      (node (ref "Q4") (pin "3") (pinfunction "G_3") (pintype "passive"))
      (node (ref "Q5") (pin "3") (pinfunction "D_3") (pintype "passive"))
      (node (ref "R27") (pin "1") (pinfunction "1_1") (pintype "passive"))
    )
    (net (code "36") (name "Net-(U3-IO3)") (class "Default")
      (node (ref "TP2") (pin "1") (pinfunction "1_1") (pintype "passive"))
      (node (ref "U3") (pin "8") (pinfunction "IO3_8") (pintype "bidirectional"))
    )
    (net (code "37") (name "Net-(U3-IO4)") (class "Default")
      (node (ref "TP3") (pin "1") (pinfunction "1_1") (pintype "passive"))
      (node (ref "U3") (pin "9") (pinfunction "IO4_9") (pintype "bidirectional"))
    )
    (net (code "38") (name "Net-(U3-IO5)") (class "Default")
      (node (ref "TP4") (pin "1") (pinfunction "1_1") (pintype "passive"))
      (node (ref "U3") (pin "10") (pinfunction "IO5_10") (pintype "bidirectional"))
    )
    (net (code "39") (name "Net-(U3-IO6)") (class "Default")
      (node (ref "TP5") (pin "1") (pinfunction "1_1") (pintype "passive"))
      (node (ref "U3") (pin "11") (pinfunction "IO6_11") (pintype "bidirectional"))
    )
    (net (code "40") (name "Net-(U3-IO7)") (class "Default")
      (node (ref "R12") (pin "2") (pinfunction "2_2") (pintype "passive"))
      (node (ref "TP10") (pin "1") (pinfunction "1_1") (pintype "passive"))
      (node (ref "U3") (pin "12") (pinfunction "IO7_12") (pintype "bidirectional"))
    )
    (net (code "41") (name "Net-(U3-~{RESET})") (class "Default")
      (node (ref "R26") (pin "1") (pinfunction "1_1") (pintype "passive"))
      (node (ref "U3") (pin "13") (pinfunction "~{RESET}_13") (pintype "input"))
    )
    (net (code "42") (name "Net-(U4-CIN1+)") (class "Default")
      (node (ref "R31") (pin "1") (pinfunction "1_1") (pintype "passive"))
      (node (ref "R32") (pin "2") (pinfunction "2_2") (pintype "passive"))
      (node (ref "TP12") (pin "1") (pinfunction "1_1") (pintype "passive"))
      (node (ref "U4") (pin "10") (pinfunction "CIN1+_10") (pintype "input"))
    )
    (net (code "43") (name "Net-(U4-CIN1-)") (class "Default")
      (node (ref "R33") (pin "1") (pinfunction "1_1") (pintype "passive"))
      (node (ref "R34") (pin "2") (pinfunction "2_2") (pintype "passive"))
      (node (ref "TP11") (pin "1") (pinfunction "1_1") (pintype "passive"))
      (node (ref "U4") (pin "11") (pinfunction "CIN1-_11") (pintype "input"))
    )
    (net (code "44") (name "Net-(U4-CIN2-)") (class "Default")
      (node (ref "R33") (pin "2") (pinfunction "2_2") (pintype "passive"))
      (node (ref "U4") (pin "12") (pinfunction "REF_12") (pintype "output"))
      (node (ref "U4") (pin "9") (pinfunction "CIN2-_9") (pintype "input"))
    )
    (net (code "45") (name "Net-(U4-INHIBIT)") (class "Default")
      (node (ref "R37") (pin "1") (pinfunction "1_1") (pintype "passive"))
      (node (ref "U4") (pin "5") (pinfunction "INHIBIT_5") (pintype "input"))
    )
    (net (code "46") (name "Net-(U4-IOUT)") (class "Default")
      (node (ref "R31") (pin "2") (pinfunction "2_2") (pintype "passive"))
      (node (ref "U4") (pin "14") (pinfunction "IOUT_14") (pintype "output"))
    )
    (net (code "47") (name "Net-(U4-POUT)") (class "Default")
      (node (ref "TP6") (pin "1") (pinfunction "1_1") (pintype "passive"))
      (node (ref "U4") (pin "13") (pinfunction "POUT_13") (pintype "output"))
    )
    (net (code "48") (name "Net-(U4-RS+)") (class "Default")
      (node (ref "Q4") (pin "1") (pinfunction "D_1") (pintype "passive"))
      (node (ref "Q4") (pin "2") (pinfunction "D_2") (pintype "passive"))
      (node (ref "Q4") (pin "5") (pinfunction "D_5") (pintype "passive"))
      (node (ref "Q4") (pin "6") (pinfunction "D_6") (pintype "passive"))
      (node (ref "R29") (pin "1") (pinfunction "1_1") (pintype "passive"))
      (node (ref "U4") (pin "16") (pinfunction "RS+_16") (pintype "passive"))
    )
    (net (code "49") (name "Net-(U5-PG)") (class "Default")
      (node (ref "TP16") (pin "1") (pinfunction "1_1") (pintype "passive"))
      (node (ref "U5") (pin "13") (pinfunction "PG_13") (pintype "open_collector"))
    )
    (net (code "50") (name "Net-(U5-SYNC)") (class "Default")
      (node (ref "R10") (pin "2") (pinfunction "2_2") (pintype "passive"))
      (node (ref "R7") (pin "1") (pinfunction "1_1") (pintype "passive"))
      (node (ref "TP19") (pin "1") (pinfunction "1_1") (pintype "passive"))
      (node (ref "U5") (pin "5") (pinfunction "SYNC_5") (pintype "input"))
    )
    (net (code "51") (name "ON{slash}~{OFF}") (class "Default")
      (node (ref "Q5") (pin "1") (pinfunction "G_1") (pintype "passive"))
      (node (ref "R28") (pin "2") (pinfunction "2_2") (pintype "passive"))
      (node (ref "TP13") (pin "1") (pinfunction "1_1") (pintype "passive"))
      (node (ref "U3") (pin "4") (pinfunction "IO0_4") (pintype "bidirectional"))
    )
    (net (code "52") (name "OPD_PWR") (class "Default")
      (node (ref "J6") (pin "19") (pinfunction "19_19") (pintype "passive"))
      (node (ref "J6") (pin "20") (pinfunction "20_20") (pintype "passive"))
      (node (ref "R4") (pin "1") (pinfunction "1_1") (pintype "passive"))
    )
    (net (code "53") (name "OPD_SCL") (class "Default")
      (node (ref "J6") (pin "17") (pinfunction "17_17") (pintype "passive"))
      (node (ref "J6") (pin "18") (pinfunction "18_18") (pintype "passive"))
      (node (ref "R24") (pin "1") (pinfunction "1_1") (pintype "passive"))
    )
    (net (code "54") (name "OPD_SDA") (class "Default")
      (node (ref "J6") (pin "15") (pinfunction "15_15") (pintype "passive"))
      (node (ref "J6") (pin "16") (pinfunction "16_16") (pintype "passive"))
      (node (ref "R25") (pin "1") (pinfunction "1_1") (pintype "passive"))
    )
    (net (code "55") (name "PEN-SCL-FILT") (class "Default")
      (node (ref "R13") (pin "1") (pinfunction "1_1") (pintype "passive"))
      (node (ref "R21") (pin "1") (pinfunction "1_1") (pintype "passive"))
      (node (ref "R24") (pin "2") (pinfunction "2_2") (pintype "passive"))
      (node (ref "R6") (pin "1") (pinfunction "1_1") (pintype "passive"))
      (node (ref "TP18") (pin "1") (pinfunction "1_1") (pintype "passive"))
      (node (ref "U3") (pin "15") (pinfunction "SCL_15") (pintype "input"))
    )
    (net (code "56") (name "PEN-SDA-FILT") (class "Default")
      (node (ref "Q1") (pin "6") (pinfunction "D_6") (pintype "passive"))
      (node (ref "R16") (pin "1") (pinfunction "1_1") (pintype "passive"))
      (node (ref "R19") (pin "2") (pinfunction "2_2") (pintype "passive"))
      (node (ref "R23") (pin "2") (pinfunction "2_2") (pintype "passive"))
      (node (ref "R9") (pin "2") (pinfunction "2_2") (pintype "passive"))
      (node (ref "TP20") (pin "1") (pinfunction "1_1") (pintype "passive"))
      (node (ref "U3") (pin "16") (pinfunction "SDA_16") (pintype "bidirectional"))
    )
    (net (code "57") (name "SPARE1") (class "Default")
      (node (ref "J6") (pin "13") (pinfunction "13_13") (pintype "passive"))
      (node (ref "J6") (pin "14") (pinfunction "14_14") (pintype "passive"))
      (node (ref "JP11") (pin "8") (pinfunction "8_8") (pintype "passive"))
    )
    (net (code "58") (name "SPARE2") (class "Default")
      (node (ref "J6") (pin "11") (pinfunction "11_11") (pintype "passive"))
      (node (ref "J6") (pin "12") (pinfunction "12_12") (pintype "passive"))
      (node (ref "JP11") (pin "7") (pinfunction "7_7") (pintype "passive"))
    )
    (net (code "59") (name "SPARE3") (class "Default")
      (node (ref "J6") (pin "10") (pinfunction "10_10") (pintype "passive"))
      (node (ref "J6") (pin "9") (pinfunction "9_9") (pintype "passive"))
      (node (ref "JP11") (pin "6") (pinfunction "6_6") (pintype "passive"))
    )
    (net (code "60") (name "SPARE4") (class "Default")
      (node (ref "J6") (pin "7") (pinfunction "7_7") (pintype "passive"))
      (node (ref "J6") (pin "8") (pinfunction "8_8") (pintype "passive"))
      (node (ref "JP11") (pin "5") (pinfunction "5_5") (pintype "passive"))
    )
    (net (code "61") (name "SPARE5") (class "Default")
      (node (ref "J6") (pin "5") (pinfunction "5_5") (pintype "passive"))
      (node (ref "J6") (pin "6") (pinfunction "6_6") (pintype "passive"))
      (node (ref "JP11") (pin "4") (pinfunction "4_4") (pintype "passive"))
    )
    (net (code "62") (name "SPARE6") (class "Default")
      (node (ref "J6") (pin "3") (pinfunction "3_3") (pintype "passive"))
      (node (ref "J6") (pin "4") (pinfunction "4_4") (pintype "passive"))
      (node (ref "JP11") (pin "3") (pinfunction "3_3") (pintype "passive"))
    )
    (net (code "63") (name "SPARE7") (class "Default")
      (node (ref "J6") (pin "1") (pinfunction "1_1") (pintype "passive"))
      (node (ref "J6") (pin "2") (pinfunction "2_2") (pintype "passive"))
      (node (ref "JP11") (pin "2") (pinfunction "2_2") (pintype "passive"))
    )
    (net (code "64") (name "VBUS") (class "Default")
      (node (ref "J6") (pin "25") (pinfunction "25_25") (pintype "passive"))
      (node (ref "J6") (pin "26") (pinfunction "26_26") (pintype "passive"))
      (node (ref "J6") (pin "27") (pinfunction "27_27") (pintype "passive"))
      (node (ref "J6") (pin "28") (pinfunction "28_28") (pintype "passive"))
      (node (ref "JP10") (pin "1") (pinfunction "1_1") (pintype "passive"))
      (node (ref "JP10") (pin "2") (pinfunction "2_2") (pintype "passive"))
      (node (ref "JP10") (pin "3") (pinfunction "3_3") (pintype "passive"))
      (node (ref "JP10") (pin "4") (pinfunction "4_4") (pintype "passive"))
      (node (ref "Q4") (pin "4") (pinfunction "S_4") (pintype "passive"))
      (node (ref "R27") (pin "2") (pinfunction "2_2") (pintype "passive"))
    )
    (net (code "65") (name "VBUSP") (class "Default")
      (node (ref "C10") (pin "1") (pinfunction "1_1") (pintype "passive"))
      (node (ref "C2") (pin "2") (pinfunction "2_2") (pintype "passive"))
      (node (ref "C7") (pin "1") (pinfunction "1_1") (pintype "passive"))
      (node (ref "JP1") (pin "5") (pinfunction "5_5") (pintype "passive"))
      (node (ref "JP3") (pin "1") (pinfunction "1_1") (pintype "passive"))
      (node (ref "JP3") (pin "2") (pinfunction "2_2") (pintype "passive"))
      (node (ref "JP3") (pin "3") (pinfunction "3_3") (pintype "passive"))
      (node (ref "Q3") (pin "1") (pinfunction "D_1") (pintype "passive"))
      (node (ref "Q3") (pin "2") (pinfunction "D_2") (pintype "passive"))
      (node (ref "Q3") (pin "5") (pinfunction "D_5") (pintype "passive"))
      (node (ref "Q3") (pin "6") (pinfunction "D_6") (pintype "passive"))
      (node (ref "R1") (pin "2") (pinfunction "2_2") (pintype "passive"))
      (node (ref "R7") (pin "2") (pinfunction "2_2") (pintype "passive"))
      (node (ref "TP9") (pin "1") (pinfunction "1_1") (pintype "passive"))
      (node (ref "U5") (pin "2") (pinfunction "VIN_2") (pintype "power_in"))
      (node (ref "U5") (pin "3") (pinfunction "VIN_3") (pintype "power_in"))
      (node (ref "U5") (pin "4") (pinfunction "EN_4") (pintype "input"))
      (node (ref "U5") (pin "8") (pinfunction "VIN_8") (pintype "power_in"))
    )
    (net (code "66") (name "VPD") (class "Default")
      (node (ref "C1") (pin "2") (pinfunction "2_2") (pintype "passive"))
      (node (ref "C8") (pin "1") (pinfunction "1_1") (pintype "passive"))
      (node (ref "Q1") (pin "2") (pinfunction "S_2") (pintype "passive"))
      (node (ref "R11") (pin "2") (pinfunction "2_2") (pintype "passive"))
      (node (ref "R18") (pin "2") (pinfunction "2_2") (pintype "passive"))
      (node (ref "R20") (pin "2") (pinfunction "2_2") (pintype "passive"))
      (node (ref "R26") (pin "2") (pinfunction "2_2") (pintype "passive"))
      (node (ref "R38") (pin "2") (pinfunction "2_2") (pintype "passive"))
      (node (ref "R4") (pin "2") (pinfunction "2_2") (pintype "passive"))
      (node (ref "R5") (pin "2") (pinfunction "2_2") (pintype "passive"))
      (node (ref "TP1") (pin "1") (pinfunction "1_1") (pintype "passive"))
      (node (ref "U3") (pin "14") (pinfunction "V+_14") (pintype "power_in"))
    )
    (net (code "67") (name "unconnected-(JP11-Pad1)") (class "Default")
      (node (ref "JP11") (pin "1") (pinfunction "1_1") (pintype "passive"))
    )
    (net (code "68") (name "~{FAULT}") (class "Default")
      (node (ref "Q6") (pin "3") (pinfunction "D_3") (pintype "passive"))
      (node (ref "R38") (pin "1") (pinfunction "1_1") (pintype "passive"))
      (node (ref "TP8") (pin "1") (pinfunction "1_1") (pintype "passive"))
      (node (ref "U3") (pin "7") (pinfunction "IO2_7") (pintype "bidirectional"))
    )
    (net (code "69") (name "~{SHUTDOWN}") (class "Default")
      (node (ref "J6") (pin "39") (pinfunction "39_39") (pintype "passive"))
      (node (ref "J6") (pin "40") (pinfunction "40_40") (pintype "passive"))
      (node (ref "JP1") (pin "3") (pinfunction "3_3") (pintype "passive"))
      (node (ref "JP10") (pin "10") (pinfunction "10_10") (pintype "passive"))
      (node (ref "JP10") (pin "9") (pinfunction "9_9") (pintype "passive"))
    )
  )
)
